# bbf-eurojacks.net
KiCad netlist of a schematic drawn in EAGLE
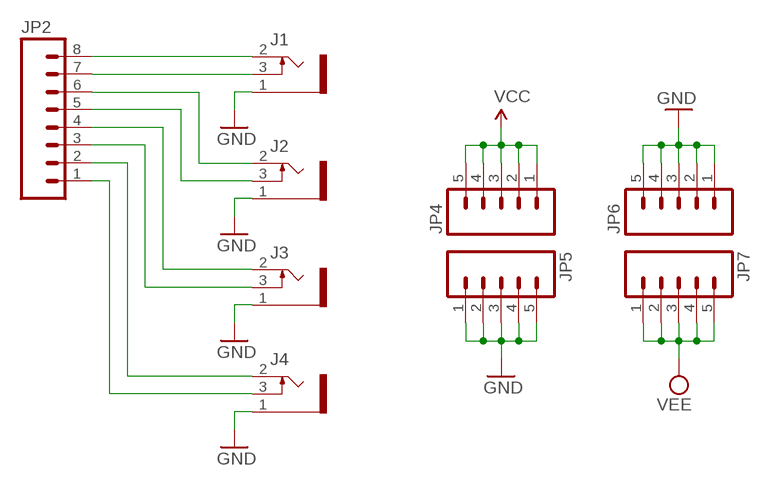
[diagram p0: schematic, sheet 1]

(export (version "E")
  (design (tool "Eeschema 10.0.6"))
  (components
    (comp (ref "J1")
      (value "1502_03SLOTTED")
      (footprint "eagle-import:1502_03_SLOTTED")
      (libsource (lib "eagle-import") (part "1502_03SLOTTED"))
    )
    (comp (ref "J2")
      (value "1502_03SLOTTED")
      (footprint "eagle-import:1502_03_SLOTTED")
      (libsource (lib "eagle-import") (part "1502_03SLOTTED"))
    )
    (comp (ref "J3")
      (value "1502_03SLOTTED")
      (footprint "eagle-import:1502_03_SLOTTED")
      (libsource (lib "eagle-import") (part "1502_03SLOTTED"))
    )
    (comp (ref "J4")
      (value "1502_03SLOTTED")
      (footprint "eagle-import:1502_03_SLOTTED")
      (libsource (lib "eagle-import") (part "1502_03SLOTTED"))
    )
    (comp (ref "JP2")
      (value "M08")
      (footprint "eagle-import:1X08")
      (libsource (lib "eagle-import") (part "M08"))
    )
    (comp (ref "JP4")
      (value "M05PTH")
      (footprint "eagle-import:1X05")
      (libsource (lib "eagle-import") (part "M05PTH"))
    )
    (comp (ref "JP5")
      (value "M05PTH")
      (footprint "eagle-import:1X05")
      (libsource (lib "eagle-import") (part "M05PTH"))
    )
    (comp (ref "JP6")
      (value "M05PTH")
      (footprint "eagle-import:1X05")
      (libsource (lib "eagle-import") (part "M05PTH"))
    )
    (comp (ref "JP7")
      (value "M05PTH")
      (footprint "eagle-import:1X05")
      (libsource (lib "eagle-import") (part "M05PTH"))
    )
  )
  (nets
    (net (code "1") (name "GND") (class "Default")
      (node (ref "J1") (pin "1") (pinfunction "1_1") (pintype "passive"))
      (node (ref "J2") (pin "1") (pinfunction "1_1") (pintype "passive"))
      (node (ref "J3") (pin "1") (pinfunction "1_1") (pintype "passive"))
      (node (ref "J4") (pin "1") (pinfunction "1_1") (pintype "passive"))
      (node (ref "JP5") (pin "1") (pinfunction "1_1") (pintype "passive"))
      (node (ref "JP5") (pin "2") (pinfunction "2_2") (pintype "passive"))
      (node (ref "JP5") (pin "3") (pinfunction "3_3") (pintype "passive"))
      (node (ref "JP5") (pin "4") (pinfunction "4_4") (pintype "passive"))
      (node (ref "JP5") (pin "5") (pinfunction "5_5") (pintype "passive"))
      (node (ref "JP6") (pin "1") (pinfunction "1_1") (pintype "passive"))
      (node (ref "JP6") (pin "2") (pinfunction "2_2") (pintype "passive"))
      (node (ref "JP6") (pin "3") (pinfunction "3_3") (pintype "passive"))
      (node (ref "JP6") (pin "4") (pinfunction "4_4") (pintype "passive"))
      (node (ref "JP6") (pin "5") (pinfunction "5_5") (pintype "passive"))
    )
    (net (code "2") (name "Net-(J1-Pad2)") (class "Default")
      (node (ref "J1") (pin "2") (pinfunction "2_2") (pintype "passive"))
      (node (ref "JP2") (pin "8") (pinfunction "8_8") (pintype "passive"))
    )
    (net (code "3") (name "Net-(J1-Pad3)") (class "Default")
      (node (ref "J1") (pin "3") (pinfunction "3_3") (pintype "passive"))
      (node (ref "JP2") (pin "7") (pinfunction "7_7") (pintype "passive"))
    )
    (net (code "4") (name "Net-(J2-Pad2)") (class "Default")
      (node (ref "J2") (pin "2") (pinfunction "2_2") (pintype "passive"))
      (node (ref "JP2") (pin "6") (pinfunction "6_6") (pintype "passive"))
    )
    (net (code "5") (name "Net-(J2-Pad3)") (class "Default")
      (node (ref "J2") (pin "3") (pinfunction "3_3") (pintype "passive"))
      (node (ref "JP2") (pin "5") (pinfunction "5_5") (pintype "passive"))
    )
    (net (code "6") (name "Net-(J3-Pad2)") (class "Default")
      (node (ref "J3") (pin "2") (pinfunction "2_2") (pintype "passive"))
      (node (ref "JP2") (pin "4") (pinfunction "4_4") (pintype "passive"))
    )
    (net (code "7") (name "Net-(J3-Pad3)") (class "Default")
      (node (ref "J3") (pin "3") (pinfunction "3_3") (pintype "passive"))
      (node (ref "JP2") (pin "3") (pinfunction "3_3") (pintype "passive"))
    )
    (net (code "8") (name "Net-(J4-Pad2)") (class "Default")
      (node (ref "J4") (pin "2") (pinfunction "2_2") (pintype "passive"))
      (node (ref "JP2") (pin "2") (pinfunction "2_2") (pintype "passive"))
    )
    (net (code "9") (name "Net-(J4-Pad3)") (class "Default")
      (node (ref "J4") (pin "3") (pinfunction "3_3") (pintype "passive"))
      (node (ref "JP2") (pin "1") (pinfunction "1_1") (pintype "passive"))
    )
    (net (code "10") (name "VCC") (class "Default")
      (node (ref "JP4") (pin "1") (pinfunction "1_1") (pintype "passive"))
      (node (ref "JP4") (pin "2") (pinfunction "2_2") (pintype "passive"))
      (node (ref "JP4") (pin "3") (pinfunction "3_3") (pintype "passive"))
      (node (ref "JP4") (pin "4") (pinfunction "4_4") (pintype "passive"))
      (node (ref "JP4") (pin "5") (pinfunction "5_5") (pintype "passive"))
    )
    (net (code "11") (name "VEE") (class "Default")
      (node (ref "JP7") (pin "1") (pinfunction "1_1") (pintype "passive"))
      (node (ref "JP7") (pin "2") (pinfunction "2_2") (pintype "passive"))
      (node (ref "JP7") (pin "3") (pinfunction "3_3") (pintype "passive"))
      (node (ref "JP7") (pin "4") (pinfunction "4_4") (pintype "passive"))
      (node (ref "JP7") (pin "5") (pinfunction "5_5") (pintype "passive"))
    )
  )
)
